# rpi_fan_control.net
KiCad netlist of a schematic drawn in Altium Designer
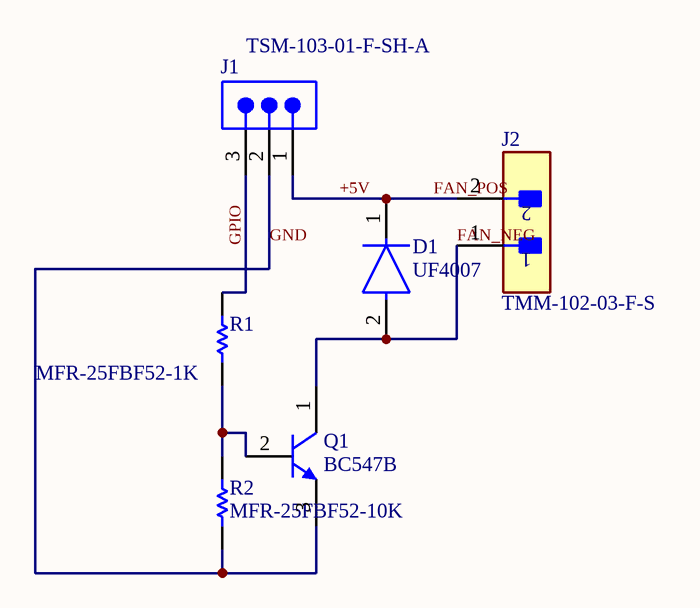
[diagram p0: rpi fan control.SchDoc]

(export (version "E")
  (design (tool "Eeschema 10.0.6"))
  (components
    (comp (ref "D1")
      (value "UF4007")
      (description "Diode Ultra Fast Recovery Rectifier 1K Volt 1A 2-Pin DO-41 Tape and Reel")
      (fields (field (name "MANUFACTURER") "onsemi") (field (name "VOLTAGE") "1kV"))
      (libsource (lib "rpi fan control") (part "UF4007"))
    )
    (comp (ref "J1")
      (value "TSM-103-01-F-SH-A")
      (description "Conn Unshrouded Header HDR 3 POS 2.54mm Solder RA SMD Tube")
      (fields (field (name "MANUFACTURER") "Samtec"))
      (libsource (lib "rpi fan control") (part "TSM-103-01-F-SH-A"))
    )
    (comp (ref "J2")
      (value "TMM-102-03-F-S")
      (description "Pin Header, Board-to-Board, Wire-to-Board, 2 mm, 1 Rows, 2 Contacts, Through Hole, TMM")
      (fields (field (name "MANUFACTURER") "Samtec"))
      (libsource (lib "rpi fan control") (part "TMM-102-03-F-S"))
    )
    (comp (ref "Q1")
      (value "BC547B")
      (description "BC547 Series 45 V CE Breakdown .1 A NPN Epitaxial Silicon Transistor - TO-92")
      (fields (field (name "MANUFACTURER") "onsemi") (field (name "VOLTAGE") "40V"))
      (libsource (lib "rpi fan control") (part "BC547B"))
    )
    (comp (ref "R1")
      (value "MFR-25FBF52-1K")
      (description "Fixed Resistor, Metal Film, 0.25W, 1000ohm, 250V, 1% +/-Tol, 100ppm/Cel, Through Hole Mount")
      (fields (field (name "MANUFACTURER") "Yageo Group") (field (name "TOLERANCE") "1%"))
      (libsource (lib "rpi fan control") (part "MFR-25FBF52-1K"))
    )
    (comp (ref "R2")
      (value "MFR-25FBF52-10K")
      (description "Fixed Resistor, Metal Film, 0.25W, 10000ohm, 250V, 1% +/-Tol, 100ppm/Cel, Through Hole Mount")
      (fields (field (name "MANUFACTURER") "Yageo Group") (field (name "TOLERANCE") "1%"))
      (libsource (lib "rpi fan control") (part "MFR-25FBF52-10K"))
    )
  )
  (nets
    (net (code "1") (name "/+5V") (class "Default")
      (node (ref "D1") (pin "1") (pinfunction "C_1") (pintype "passive"))
      (node (ref "J1") (pin "1") (pinfunction "1_1") (pintype "passive"))
      (node (ref "J2") (pin "2") (pinfunction "2_2") (pintype "passive"))
    )
    (net (code "2") (name "/FAN_NEG") (class "Default")
      (node (ref "D1") (pin "2") (pinfunction "A_2") (pintype "passive"))
      (node (ref "J2") (pin "1") (pinfunction "1_1") (pintype "passive"))
      (node (ref "Q1") (pin "1") (pinfunction "C_1") (pintype "passive"))
    )
    (net (code "3") (name "/GND") (class "Default")
      (node (ref "J1") (pin "2") (pinfunction "2_2") (pintype "passive"))
      (node (ref "Q1") (pin "3") (pinfunction "E_3") (pintype "passive"))
      (node (ref "R2") (pin "1") (pinfunction "1_1") (pintype "passive"))
    )
    (net (code "4") (name "/GPIO") (class "Default")
      (node (ref "J1") (pin "3") (pinfunction "3_3") (pintype "passive"))
      (node (ref "R1") (pin "1") (pinfunction "1_1") (pintype "passive"))
    )
    (net (code "5") (name "Net-(Q1-B)") (class "Default")
      (node (ref "Q1") (pin "2") (pinfunction "B_2") (pintype "passive"))
      (node (ref "R1") (pin "2") (pinfunction "2_2") (pintype "passive"))
      (node (ref "R2") (pin "2") (pinfunction "2_2") (pintype "passive"))
    )
  )
)
